# SCH_Tiny_printer_small_2024-12-05.net
KiCad netlist of a schematic drawn in EasyEDA
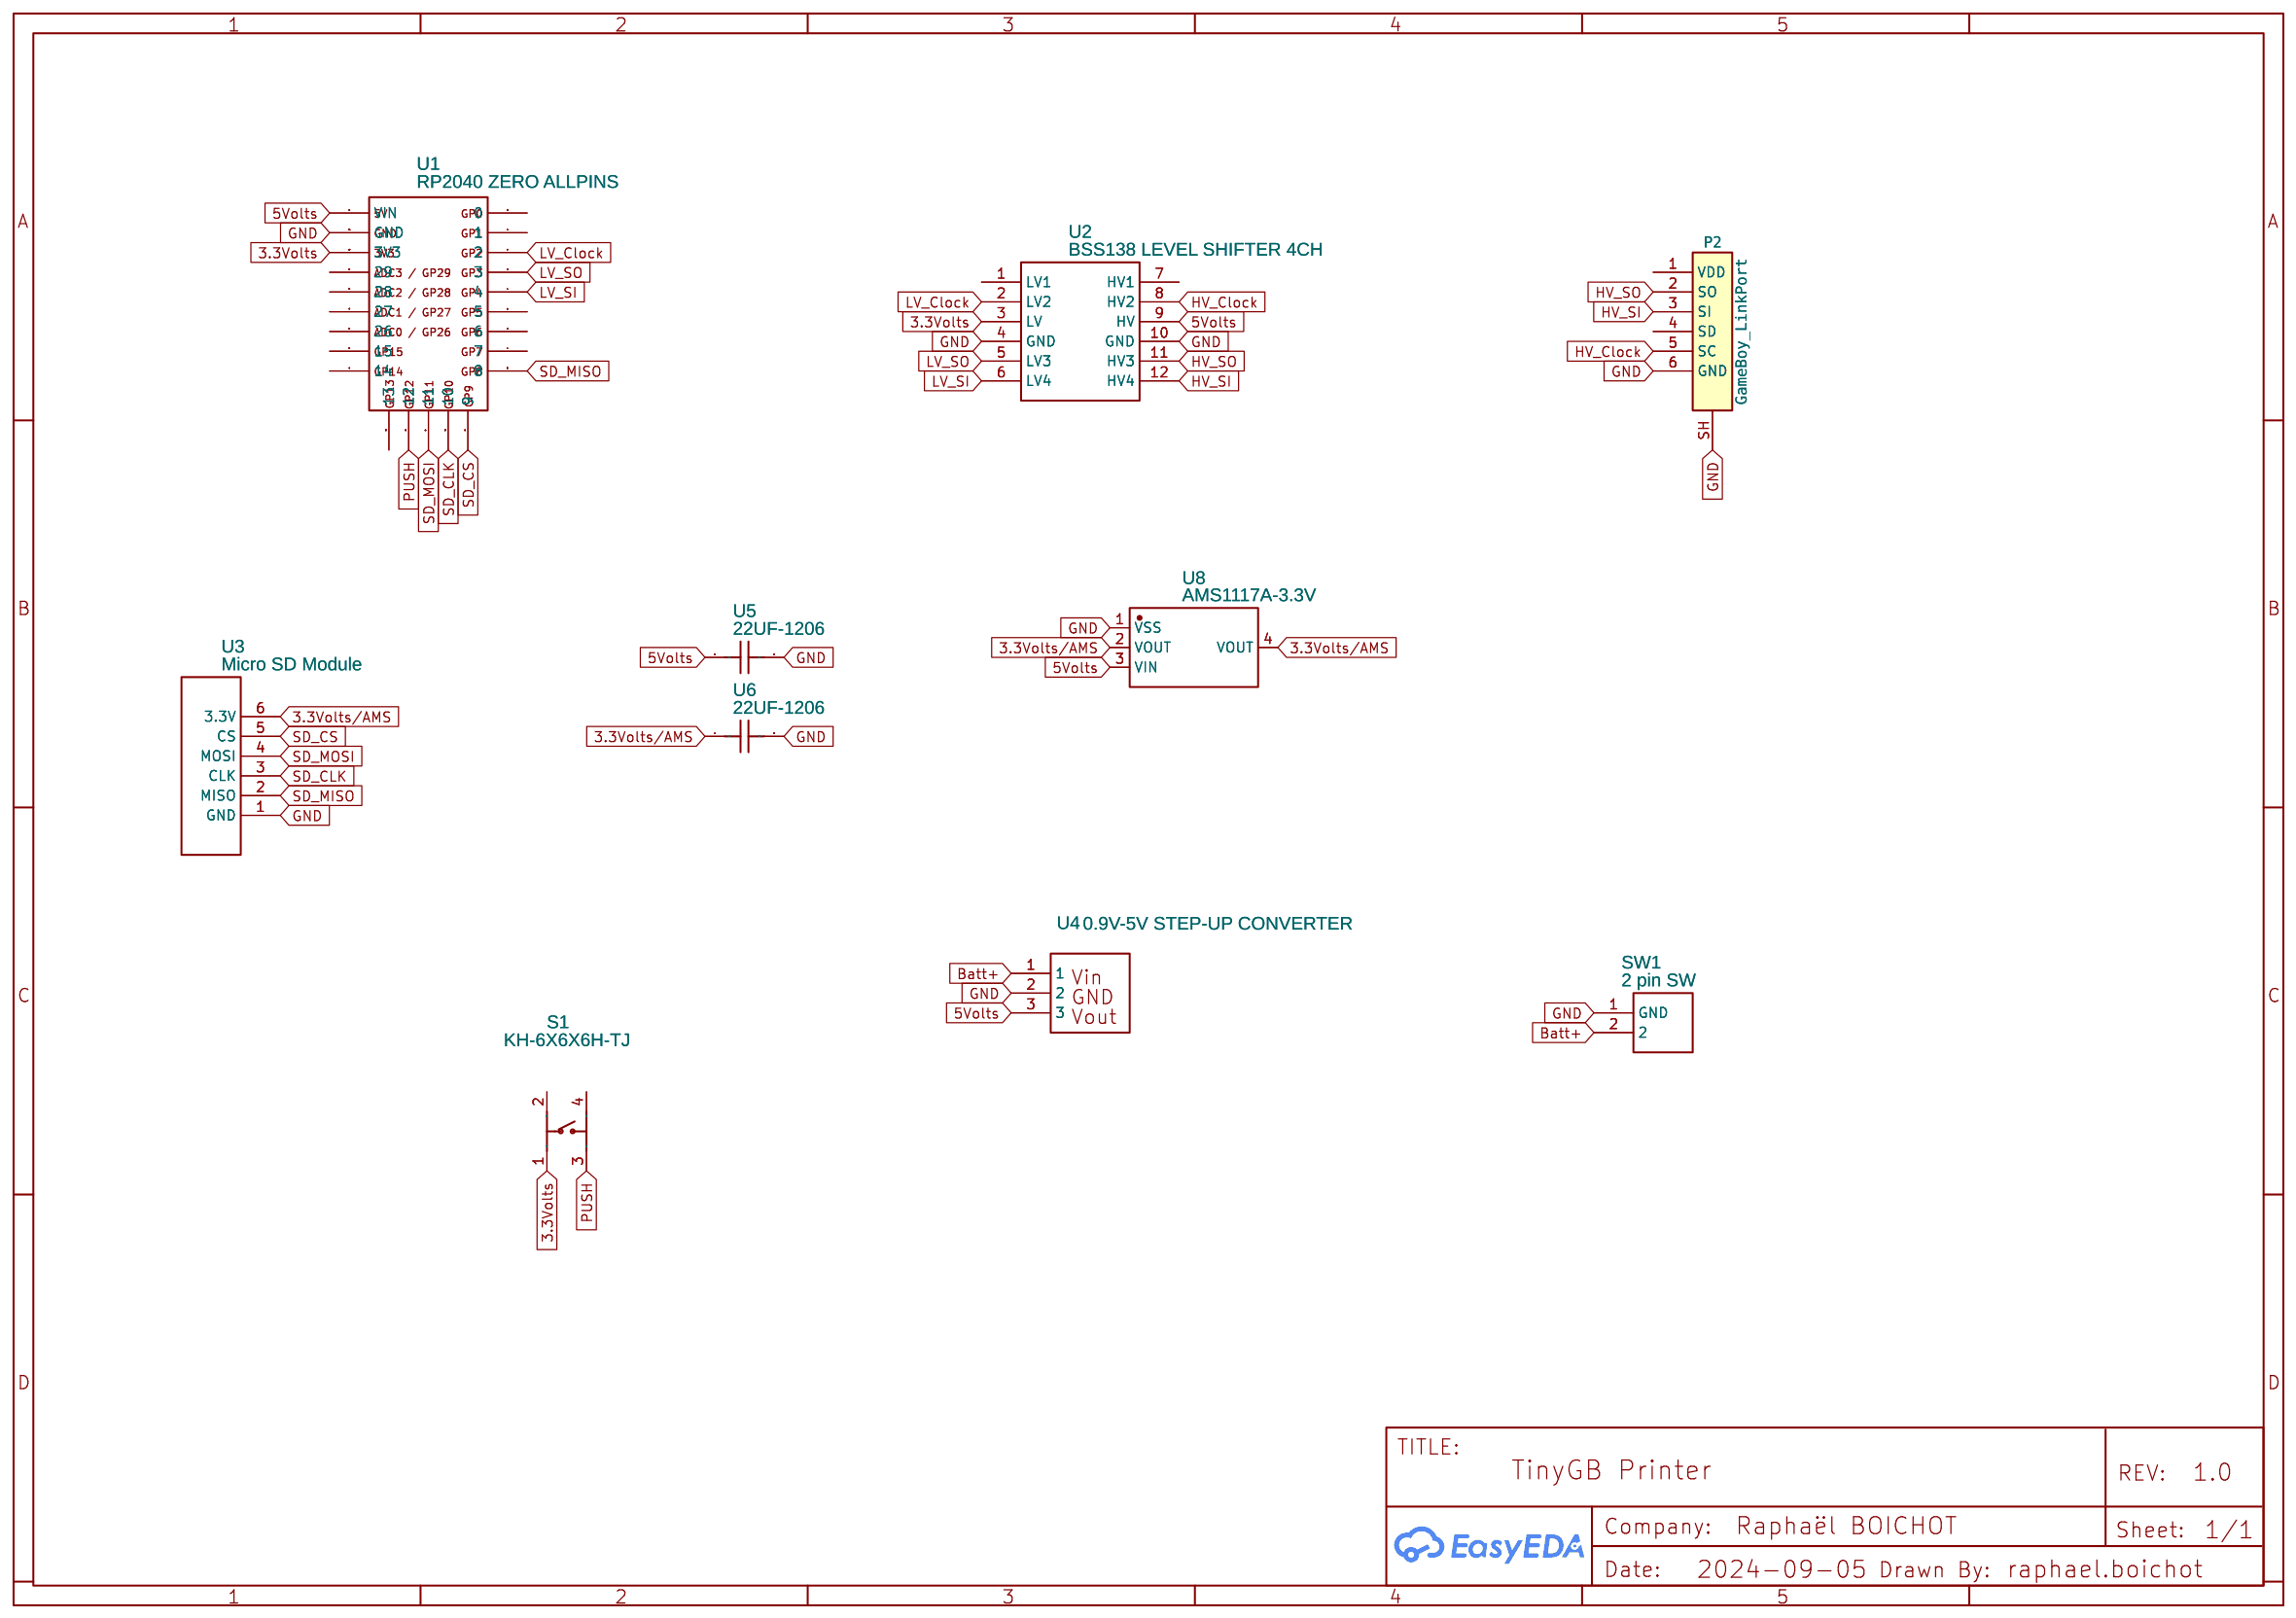
[diagram p0: schematic sheet]

(export (version "E")
  (design (tool "Eeschema 10.0.6"))
  (components
    (comp (ref "P2") (value "GameBoy_LinkPort") (libsource (lib "") (part "Unknown_860_-645")))
    (comp (ref "S1")
      (value "KH-6X6X6H-TJ")
      (fields (field (name "Manufacturer") "kinghelm(金航标)"))
      (libsource (lib "") (part "KH-6X6X6H-TJ"))
    )
    (comp (ref "SW1")
      (value "2 pin SW")
      (fields (field (name "Manufacturer") "NA"))
      (libsource (lib "") (part "2 pin SW"))
    )
    (comp (ref "U1")
      (value "RP2040 ZERO ALLPINS")
      (fields (field (name "Manufacturer Part") "RP2040 Zero") (field (name "Manufacturer") "Waveshare"))
      (libsource (lib "") (part "RP2040 ZERO ALLPINS"))
    )
    (comp (ref "U2")
      (value "BSS138 LEVEL SHIFTER 4CH")
      (fields (field (name "Manufacturer Part") "BSS138") (field (name "Manufacturer") "ON Semiconductor"))
      (libsource (lib "") (part "BSS138 LEVEL SHIFTER 4CH"))
    )
    (comp (ref "U3") (value "Micro SD Module") (libsource (lib "") (part "Micro SD Module")))
    (comp (ref "U4")
      (value "0.9V-5V STEP-UP CONVERTER")
      (fields (field (name "Manufacturer") "Generic"))
      (libsource (lib "") (part "0.9V-5V STEP-UP CONVERTER"))
    )
    (comp (ref "U5")
      (value "22UF-1206")
      (fields (field (name "Manufacturer Part") "220UF-1206"))
      (libsource (lib "") (part "220UF-1206"))
    )
    (comp (ref "U6")
      (value "22UF-1206")
      (fields (field (name "Manufacturer Part") "220UF-1206"))
      (libsource (lib "") (part "220UF-1206"))
    )
    (comp (ref "U8")
      (value "AMS1117A-3.3V")
      (fields (field (name "Manufacturer") "HX(恒佳兴)"))
      (libsource (lib "") (part "AMS1117A-3.3V"))
    )
  )
  (nets
    (net (code "1") (name "3.3Volts") (class "Default")
      (node (ref "S1") (pin "1") (pinfunction "1_1") (pintype "unspecified"))
      (node (ref "U1") (pin "3V3") (pinfunction "3V3_3V3") (pintype "unspecified"))
      (node (ref "U2") (pin "3") (pinfunction "LV_3") (pintype "passive"))
    )
    (net (code "2") (name "3.3Volts{slash}AMS") (class "Default")
      (node (ref "U3") (pin "6") (pinfunction "3.3V_6") (pintype "unspecified"))
      (node (ref "U6") (pin "1") (pinfunction "1_1") (pintype "unspecified"))
      (node (ref "U8") (pin "2") (pinfunction "VOUT_2") (pintype "unspecified"))
      (node (ref "U8") (pin "4") (pinfunction "VOUT_4") (pintype "unspecified"))
    )
    (net (code "3") (name "5Volts") (class "Default")
      (node (ref "U1") (pin "VIN") (pinfunction "VIN_VIN") (pintype "unspecified"))
      (node (ref "U2") (pin "9") (pinfunction "HV_9") (pintype "passive"))
      (node (ref "U4") (pin "3") (pinfunction "3_3") (pintype "unspecified"))
      (node (ref "U5") (pin "1") (pinfunction "1_1") (pintype "unspecified"))
      (node (ref "U8") (pin "3") (pinfunction "VIN_3") (pintype "unspecified"))
    )
    (net (code "4") (name "Batt+") (class "Default")
      (node (ref "SW1") (pin "2") (pinfunction "2_2") (pintype "unspecified"))
      (node (ref "U4") (pin "1") (pinfunction "1_1") (pintype "unspecified"))
    )
    (net (code "5") (name "GND") (class "Default")
      (node (ref "P2") (pin "6") (pinfunction "GND_6") (pintype "unspecified"))
      (node (ref "P2") (pin "SH") (pintype "unspecified"))
      (node (ref "SW1") (pin "1") (pinfunction "GND_1") (pintype "unspecified"))
      (node (ref "U1") (pin "GND") (pinfunction "GND_GND") (pintype "unspecified"))
      (node (ref "U2") (pin "10") (pinfunction "GND_10") (pintype "passive"))
      (node (ref "U2") (pin "4") (pinfunction "GND_4") (pintype "passive"))
      (node (ref "U3") (pin "1") (pinfunction "GND_1") (pintype "unspecified"))
      (node (ref "U4") (pin "2") (pinfunction "2_2") (pintype "unspecified"))
      (node (ref "U5") (pin "2") (pinfunction "2_2") (pintype "unspecified"))
      (node (ref "U6") (pin "2") (pinfunction "2_2") (pintype "unspecified"))
      (node (ref "U8") (pin "1") (pinfunction "VSS_1") (pintype "unspecified"))
    )
    (net (code "6") (name "HV_Clock") (class "Default")
      (node (ref "P2") (pin "5") (pinfunction "SC_5") (pintype "unspecified"))
      (node (ref "U2") (pin "8") (pinfunction "HV2_8") (pintype "output"))
    )
    (net (code "7") (name "HV_SI") (class "Default")
      (node (ref "P2") (pin "3") (pinfunction "SI_3") (pintype "unspecified"))
      (node (ref "U2") (pin "12") (pinfunction "HV4_12") (pintype "output"))
    )
    (net (code "8") (name "HV_SO") (class "Default")
      (node (ref "P2") (pin "2") (pinfunction "SO_2") (pintype "unspecified"))
      (node (ref "U2") (pin "11") (pinfunction "HV3_11") (pintype "output"))
    )
    (net (code "9") (name "LV_Clock") (class "Default")
      (node (ref "U1") (pin "2") (pinfunction "2_2") (pintype "unspecified"))
      (node (ref "U2") (pin "2") (pinfunction "LV2_2") (pintype "input"))
    )
    (net (code "10") (name "LV_SI") (class "Default")
      (node (ref "U1") (pin "4") (pinfunction "4_4") (pintype "unspecified"))
      (node (ref "U2") (pin "6") (pinfunction "LV4_6") (pintype "input"))
    )
    (net (code "11") (name "LV_SO") (class "Default")
      (node (ref "U1") (pin "3") (pinfunction "3_3") (pintype "unspecified"))
      (node (ref "U2") (pin "5") (pinfunction "LV3_5") (pintype "input"))
    )
    (net (code "12") (name "PUSH") (class "Default")
      (node (ref "S1") (pin "3") (pinfunction "3_3") (pintype "unspecified"))
      (node (ref "U1") (pin "12") (pinfunction "12_12") (pintype "unspecified"))
    )
    (net (code "13") (name "SD_CLK") (class "Default")
      (node (ref "U1") (pin "10") (pinfunction "10_10") (pintype "unspecified"))
      (node (ref "U3") (pin "3") (pinfunction "CLK_3") (pintype "unspecified"))
    )
    (net (code "14") (name "SD_CS") (class "Default")
      (node (ref "U1") (pin "9") (pinfunction "9_9") (pintype "unspecified"))
      (node (ref "U3") (pin "5") (pinfunction "CS_5") (pintype "unspecified"))
    )
    (net (code "15") (name "SD_MISO") (class "Default")
      (node (ref "U1") (pin "8") (pinfunction "8_8") (pintype "unspecified"))
      (node (ref "U3") (pin "2") (pinfunction "MISO_2") (pintype "unspecified"))
    )
    (net (code "16") (name "SD_MOSI") (class "Default")
      (node (ref "U1") (pin "11") (pinfunction "11_11") (pintype "unspecified"))
      (node (ref "U3") (pin "4") (pinfunction "MOSI_4") (pintype "unspecified"))
    )
    (net (code "17") (name "unconnected-(P2-SD-Pad4)") (class "Default")
      (node (ref "P2") (pin "4") (pinfunction "SD_4") (pintype "unspecified"))
    )
    (net (code "18") (name "unconnected-(P2-VDD-Pad1)") (class "Default")
      (node (ref "P2") (pin "1") (pinfunction "VDD_1") (pintype "unspecified"))
    )
    (net (code "19") (name "unconnected-(S1-Pad2)") (class "Default")
      (node (ref "S1") (pin "2") (pinfunction "2_2") (pintype "unspecified"))
    )
    (net (code "20") (name "unconnected-(S1-Pad4)") (class "Default")
      (node (ref "S1") (pin "4") (pinfunction "4_4") (pintype "unspecified"))
    )
    (net (code "21") (name "unconnected-(U1-Pad0)") (class "Default")
      (node (ref "U1") (pin "0") (pinfunction "0_0") (pintype "unspecified"))
    )
    (net (code "22") (name "unconnected-(U1-Pad1)") (class "Default")
      (node (ref "U1") (pin "1") (pinfunction "1_1") (pintype "unspecified"))
    )
    (net (code "23") (name "unconnected-(U1-Pad5)") (class "Default")
      (node (ref "U1") (pin "5") (pinfunction "5_5") (pintype "unspecified"))
    )
    (net (code "24") (name "unconnected-(U1-Pad6)") (class "Default")
      (node (ref "U1") (pin "6") (pinfunction "6_6") (pintype "unspecified"))
    )
    (net (code "25") (name "unconnected-(U1-Pad7)") (class "Default")
      (node (ref "U1") (pin "7") (pinfunction "7_7") (pintype "unspecified"))
    )
    (net (code "26") (name "unconnected-(U1-Pad13)") (class "Default")
      (node (ref "U1") (pin "13") (pinfunction "13_13") (pintype "unspecified"))
    )
    (net (code "27") (name "unconnected-(U1-Pad14)") (class "Default")
      (node (ref "U1") (pin "14") (pinfunction "14_14") (pintype "unspecified"))
    )
    (net (code "28") (name "unconnected-(U1-Pad15)") (class "Default")
      (node (ref "U1") (pin "15") (pinfunction "15_15") (pintype "unspecified"))
    )
    (net (code "29") (name "unconnected-(U1-Pad26)") (class "Default")
      (node (ref "U1") (pin "26") (pinfunction "26_26") (pintype "unspecified"))
    )
    (net (code "30") (name "unconnected-(U1-Pad27)") (class "Default")
      (node (ref "U1") (pin "27") (pinfunction "27_27") (pintype "unspecified"))
    )
    (net (code "31") (name "unconnected-(U1-Pad28)") (class "Default")
      (node (ref "U1") (pin "28") (pinfunction "28_28") (pintype "unspecified"))
    )
    (net (code "32") (name "unconnected-(U1-Pad29)") (class "Default")
      (node (ref "U1") (pin "29") (pinfunction "29_29") (pintype "unspecified"))
    )
    (net (code "33") (name "unconnected-(U2-HV1-Pad7)") (class "Default")
      (node (ref "U2") (pin "7") (pinfunction "HV1_7") (pintype "output"))
    )
    (net (code "34") (name "unconnected-(U2-LV1-Pad1)") (class "Default")
      (node (ref "U2") (pin "1") (pinfunction "LV1_1") (pintype "input"))
    )
  )
)
